# Shield_REL_TIMER.net
KiCad netlist of a schematic drawn in EAGLE
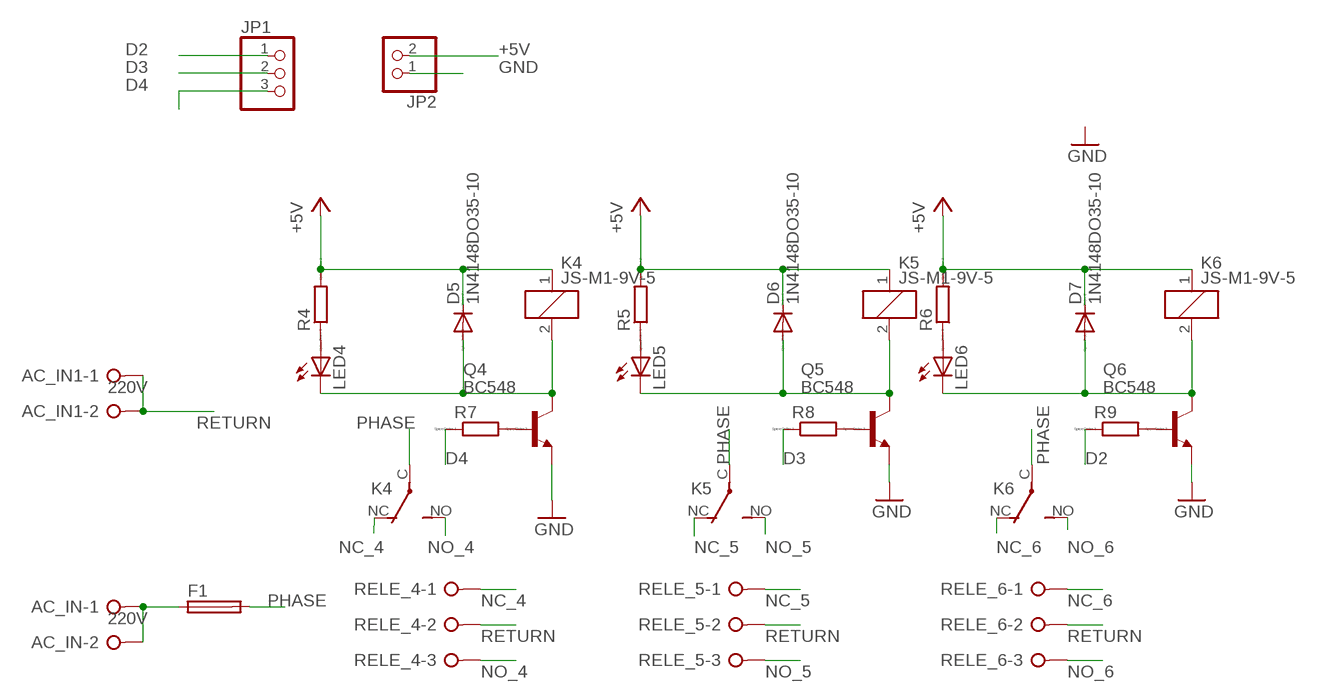
[diagram p0: schematic, sheet 1]

(export (version "E")
  (design (tool "Eeschema 10.0.6"))
  (components
    (comp (ref "AC_IN")
      (value "220V")
      (footprint "eagle-import:W237-132")
      (libsource (lib "eagle-import") (part "W237-02P"))
    )
    (comp (ref "AC_IN1")
      (value "220V")
      (footprint "eagle-import:W237-132")
      (libsource (lib "eagle-import") (part "W237-02P"))
    )
    (comp (ref "D5")
      (value "1N4148DO35-10")
      (footprint "eagle-import:DO35-10")
      (libsource (lib "eagle-import") (part "1N4148DO35-10"))
    )
    (comp (ref "D6")
      (value "1N4148DO35-10")
      (footprint "eagle-import:DO35-10")
      (libsource (lib "eagle-import") (part "1N4148DO35-10"))
    )
    (comp (ref "D7")
      (value "1N4148DO35-10")
      (footprint "eagle-import:DO35-10")
      (libsource (lib "eagle-import") (part "1N4148DO35-10"))
    )
    (comp (ref "F1")
      (value "SH22,5A")
      (footprint "eagle-import:SH22,5A")
      (fields (field (name "MPN") "0031.7701.11"))
      (libsource (lib "eagle-import") (part "SH22,5A"))
    )
    (comp (ref "JP1")
      (value "PINHD-1X3")
      (footprint "eagle-import:1X03")
      (libsource (lib "eagle-import") (part "PINHD-1X3"))
    )
    (comp (ref "JP2")
      (value "PINHD-1X2")
      (footprint "eagle-import:1X02")
      (libsource (lib "eagle-import") (part "PINHD-1X2"))
    )
    (comp (ref "K4")
      (value "JS-M1-9V-5")
      (footprint "eagle-import:JS-M")
      (libsource (lib "eagle-import") (part "JS-M1-9V-5"))
    )
    (comp (ref "K5")
      (value "JS-M1-9V-5")
      (footprint "eagle-import:JS-M")
      (libsource (lib "eagle-import") (part "JS-M1-9V-5"))
    )
    (comp (ref "K6")
      (value "JS-M1-9V-5")
      (footprint "eagle-import:JS-M")
      (libsource (lib "eagle-import") (part "JS-M1-9V-5"))
    )
    (comp (ref "LED4")
      (value "LED5MM")
      (footprint "eagle-import:LED5MM")
      (libsource (lib "eagle-import") (part "LED5MM"))
    )
    (comp (ref "LED5")
      (value "LED5MM")
      (footprint "eagle-import:LED5MM")
      (libsource (lib "eagle-import") (part "LED5MM"))
    )
    (comp (ref "LED6")
      (value "LED5MM")
      (footprint "eagle-import:LED5MM")
      (libsource (lib "eagle-import") (part "LED5MM"))
    )
    (comp (ref "Q4")
      (value "BC548")
      (footprint "eagle-import:TO92-EBC")
      (libsource (lib "eagle-import") (part "BC548"))
    )
    (comp (ref "Q5")
      (value "BC548")
      (footprint "eagle-import:TO92-EBC")
      (libsource (lib "eagle-import") (part "BC548"))
    )
    (comp (ref "Q6")
      (value "BC548")
      (footprint "eagle-import:TO92-EBC")
      (libsource (lib "eagle-import") (part "BC548"))
    )
    (comp (ref "R4")
      (value "R0204/7")
      (footprint "eagle-import:0204_7")
      (libsource (lib "eagle-import") (part "R0204/7"))
    )
    (comp (ref "R5")
      (value "R0204/7")
      (footprint "eagle-import:0204_7")
      (libsource (lib "eagle-import") (part "R0204/7"))
    )
    (comp (ref "R6")
      (value "R0204/7")
      (footprint "eagle-import:0204_7")
      (libsource (lib "eagle-import") (part "R0204/7"))
    )
    (comp (ref "R7")
      (value "R0204/7")
      (footprint "eagle-import:0204_7")
      (libsource (lib "eagle-import") (part "R0204/7"))
    )
    (comp (ref "R8")
      (value "R0204/7")
      (footprint "eagle-import:0204_7")
      (libsource (lib "eagle-import") (part "R0204/7"))
    )
    (comp (ref "R9")
      (value "R0204/7")
      (footprint "eagle-import:0204_7")
      (libsource (lib "eagle-import") (part "R0204/7"))
    )
    (comp (ref "RELE_4")
      (value "W237-03P")
      (footprint "eagle-import:W237-133")
      (libsource (lib "eagle-import") (part "W237-03P"))
    )
    (comp (ref "RELE_5")
      (value "W237-03P")
      (footprint "eagle-import:W237-133")
      (libsource (lib "eagle-import") (part "W237-03P"))
    )
    (comp (ref "RELE_6")
      (value "W237-03P")
      (footprint "eagle-import:W237-133")
      (libsource (lib "eagle-import") (part "W237-03P"))
    )
  )
  (nets
    (net (code "1") (name "+5V") (class "Default")
      (node (ref "D5") (pin "C") (pinfunction "C_C") (pintype "passive"))
      (node (ref "D6") (pin "C") (pinfunction "C_C") (pintype "passive"))
      (node (ref "D7") (pin "C") (pinfunction "C_C") (pintype "passive"))
      (node (ref "JP2") (pin "2") (pinfunction "2_2") (pintype "passive"))
      (node (ref "K4") (pin "1") (pinfunction "1_1") (pintype "passive"))
      (node (ref "K5") (pin "1") (pinfunction "1_1") (pintype "passive"))
      (node (ref "K6") (pin "1") (pinfunction "1_1") (pintype "passive"))
      (node (ref "R4") (pin "2") (pinfunction "2_2") (pintype "passive"))
      (node (ref "R5") (pin "2") (pinfunction "2_2") (pintype "passive"))
      (node (ref "R6") (pin "2") (pinfunction "2_2") (pintype "passive"))
    )
    (net (code "2") (name "/D2") (class "Default")
      (node (ref "JP1") (pin "1") (pinfunction "1_1") (pintype "passive"))
      (node (ref "R9") (pin "1") (pinfunction "1_1") (pintype "passive"))
    )
    (net (code "3") (name "/D3") (class "Default")
      (node (ref "JP1") (pin "2") (pinfunction "2_2") (pintype "passive"))
      (node (ref "R8") (pin "1") (pinfunction "1_1") (pintype "passive"))
    )
    (net (code "4") (name "/D4") (class "Default")
      (node (ref "JP1") (pin "3") (pinfunction "3_3") (pintype "passive"))
      (node (ref "R7") (pin "1") (pinfunction "1_1") (pintype "passive"))
    )
    (net (code "5") (name "/NC_4") (class "Default")
      (node (ref "K4") (pin "NC") (pinfunction "O_NC") (pintype "passive"))
      (node (ref "RELE_4") (pin "1") (pinfunction "KL_1") (pintype "passive"))
    )
    (net (code "6") (name "/NC_5") (class "Default")
      (node (ref "K5") (pin "NC") (pinfunction "O_NC") (pintype "passive"))
      (node (ref "RELE_5") (pin "1") (pinfunction "KL_1") (pintype "passive"))
    )
    (net (code "7") (name "/NC_6") (class "Default")
      (node (ref "K6") (pin "NC") (pinfunction "O_NC") (pintype "passive"))
      (node (ref "RELE_6") (pin "1") (pinfunction "KL_1") (pintype "passive"))
    )
    (net (code "8") (name "/NO_4") (class "Default")
      (node (ref "K4") (pin "NO") (pinfunction "S_NO") (pintype "passive"))
      (node (ref "RELE_4") (pin "3") (pinfunction "KL_3") (pintype "passive"))
    )
    (net (code "9") (name "/NO_5") (class "Default")
      (node (ref "K5") (pin "NO") (pinfunction "S_NO") (pintype "passive"))
      (node (ref "RELE_5") (pin "3") (pinfunction "KL_3") (pintype "passive"))
    )
    (net (code "10") (name "/NO_6") (class "Default")
      (node (ref "K6") (pin "NO") (pinfunction "S_NO") (pintype "passive"))
      (node (ref "RELE_6") (pin "3") (pinfunction "KL_3") (pintype "passive"))
    )
    (net (code "11") (name "/PHASE") (class "Default")
      (node (ref "F1") (pin "2") (pinfunction "2_2") (pintype "passive"))
      (node (ref "K4") (pin "C") (pinfunction "P_C") (pintype "passive"))
      (node (ref "K5") (pin "C") (pinfunction "P_C") (pintype "passive"))
      (node (ref "K6") (pin "C") (pinfunction "P_C") (pintype "passive"))
    )
    (net (code "12") (name "/RETURN") (class "Default")
      (node (ref "AC_IN1") (pin "1") (pinfunction "KL_1") (pintype "passive"))
      (node (ref "AC_IN1") (pin "2") (pinfunction "KL_2") (pintype "passive"))
      (node (ref "RELE_4") (pin "2") (pinfunction "KL_2") (pintype "passive"))
      (node (ref "RELE_5") (pin "2") (pinfunction "KL_2") (pintype "passive"))
      (node (ref "RELE_6") (pin "2") (pinfunction "KL_2") (pintype "passive"))
    )
    (net (code "13") (name "GND") (class "Default")
      (node (ref "JP2") (pin "1") (pinfunction "1_1") (pintype "passive"))
      (node (ref "Q4") (pin "E") (pinfunction "E_E") (pintype "passive"))
      (node (ref "Q5") (pin "E") (pinfunction "E_E") (pintype "passive"))
      (node (ref "Q6") (pin "E") (pinfunction "E_E") (pintype "passive"))
    )
    (net (code "14") (name "Net-(AC_INA-KL)") (class "Default")
      (node (ref "AC_IN") (pin "1") (pinfunction "KL_1") (pintype "passive"))
      (node (ref "AC_IN") (pin "2") (pinfunction "KL_2") (pintype "passive"))
      (node (ref "F1") (pin "1") (pinfunction "1_1") (pintype "passive"))
    )
    (net (code "15") (name "Net-(LED4-C)") (class "Default")
      (node (ref "D5") (pin "A") (pinfunction "A_A") (pintype "passive"))
      (node (ref "K4") (pin "2") (pinfunction "2_2") (pintype "passive"))
      (node (ref "LED4") (pin "K") (pinfunction "C_K") (pintype "passive"))
      (node (ref "Q4") (pin "C") (pinfunction "C_C") (pintype "passive"))
    )
    (net (code "16") (name "Net-(LED4-PadA)") (class "Default")
      (node (ref "LED4") (pin "A") (pinfunction "A_A") (pintype "passive"))
      (node (ref "R4") (pin "1") (pinfunction "1_1") (pintype "passive"))
    )
    (net (code "17") (name "Net-(LED5-C)") (class "Default")
      (node (ref "D6") (pin "A") (pinfunction "A_A") (pintype "passive"))
      (node (ref "K5") (pin "2") (pinfunction "2_2") (pintype "passive"))
      (node (ref "LED5") (pin "K") (pinfunction "C_K") (pintype "passive"))
      (node (ref "Q5") (pin "C") (pinfunction "C_C") (pintype "passive"))
    )
    (net (code "18") (name "Net-(LED5-PadA)") (class "Default")
      (node (ref "LED5") (pin "A") (pinfunction "A_A") (pintype "passive"))
      (node (ref "R5") (pin "1") (pinfunction "1_1") (pintype "passive"))
    )
    (net (code "19") (name "Net-(LED6-C)") (class "Default")
      (node (ref "D7") (pin "A") (pinfunction "A_A") (pintype "passive"))
      (node (ref "K6") (pin "2") (pinfunction "2_2") (pintype "passive"))
      (node (ref "LED6") (pin "K") (pinfunction "C_K") (pintype "passive"))
      (node (ref "Q6") (pin "C") (pinfunction "C_C") (pintype "passive"))
    )
    (net (code "20") (name "Net-(LED6-PadA)") (class "Default")
      (node (ref "LED6") (pin "A") (pinfunction "A_A") (pintype "passive"))
      (node (ref "R6") (pin "1") (pinfunction "1_1") (pintype "passive"))
    )
    (net (code "21") (name "Net-(Q4-PadB)") (class "Default")
      (node (ref "Q4") (pin "B") (pinfunction "B_B") (pintype "passive"))
      (node (ref "R7") (pin "2") (pinfunction "2_2") (pintype "passive"))
    )
    (net (code "22") (name "Net-(Q5-PadB)") (class "Default")
      (node (ref "Q5") (pin "B") (pinfunction "B_B") (pintype "passive"))
      (node (ref "R8") (pin "2") (pinfunction "2_2") (pintype "passive"))
    )
    (net (code "23") (name "Net-(Q6-PadB)") (class "Default")
      (node (ref "Q6") (pin "B") (pinfunction "B_B") (pintype "passive"))
      (node (ref "R9") (pin "2") (pinfunction "2_2") (pintype "passive"))
    )
  )
)
